# clock.net
KiCad netlist of a schematic drawn in EAGLE
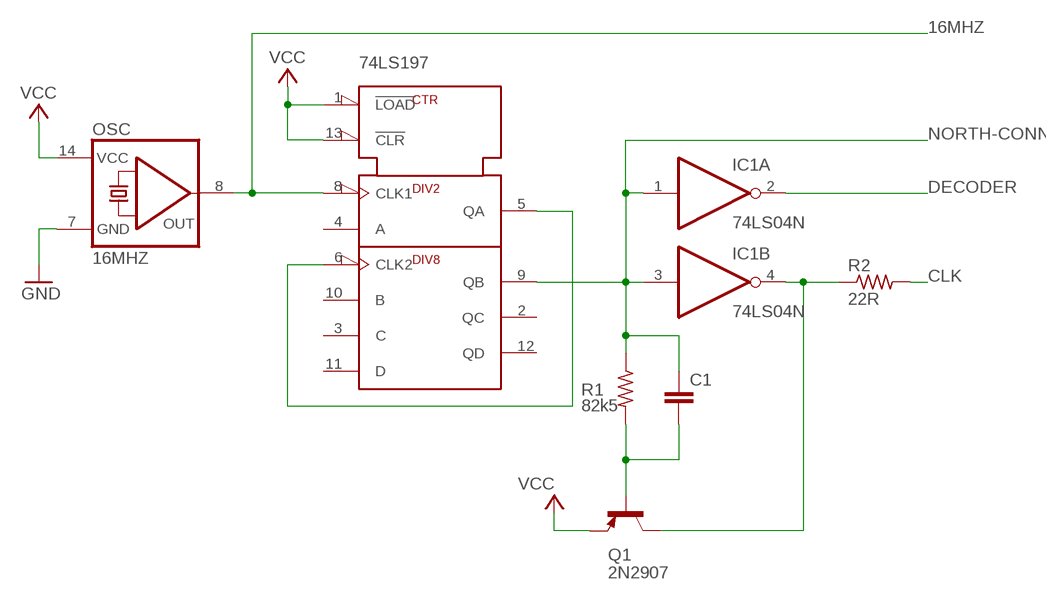
[diagram p0: schematic, sheet 1]

(export (version "E")
  (design (tool "Eeschema 10.0.6"))
  (components
    (comp (ref "C1")
      (value "C-EU025-024X044")
      (footprint "eagle-import:C025-024X044")
      (libsource (lib "eagle-import") (part "C-EU025-024X044"))
    )
    (comp (ref "IC1")
      (value "74LS04N")
      (footprint "eagle-import:DIL14")
      (libsource (lib "eagle-import") (part "7404NLS"))
    )
    (comp (ref "OSC")
      (value "16MHZ")
      (footprint "eagle-import:DIL14S")
      (libsource (lib "eagle-import") (part "QG5860"))
    )
    (comp (ref "Q1")
      (value "2N2907")
      (footprint "eagle-import:TO18")
      (libsource (lib "eagle-import") (part "2N2907"))
    )
    (comp (ref "R1")
      (value "82k5")
      (footprint "eagle-import:0207_10")
      (libsource (lib "eagle-import") (part "R-US_0207/10"))
    )
    (comp (ref "R2")
      (value "22R")
      (footprint "eagle-import:0207_10")
      (libsource (lib "eagle-import") (part "R-US_0207/10"))
    )
    (comp (ref "U$1")
      (value "74LS197")
      (footprint "eagle-import:DIL14")
      (libsource (lib "eagle-import") (part "74LS197"))
    )
  )
  (nets
    (net (code "1") (name "/16MHZ") (class "Default")
      (node (ref "OSC") (pin "8") (pinfunction "OUT_8") (pintype "output"))
      (node (ref "U$1") (pin "8") (pinfunction "CLK1_8") (pintype "input"))
    )
    (net (code "2") (name "/CLK") (class "Default")
      (node (ref "R2") (pin "2") (pinfunction "2_2") (pintype "passive"))
    )
    (net (code "3") (name "/DECODER") (class "Default")
      (node (ref "IC1") (pin "2") (pinfunction "O_2") (pintype "output"))
    )
    (net (code "4") (name "/NORTH-CONN") (class "Default")
      (node (ref "C1") (pin "1") (pinfunction "1_1") (pintype "passive"))
      (node (ref "IC1") (pin "1") (pinfunction "I_1") (pintype "input"))
      (node (ref "IC1") (pin "3") (pinfunction "I_3") (pintype "input"))
      (node (ref "R1") (pin "1") (pinfunction "1_1") (pintype "passive"))
      (node (ref "U$1") (pin "9") (pinfunction "QB_9") (pintype "output"))
    )
    (net (code "5") (name "GND") (class "Default")
      (node (ref "OSC") (pin "7") (pinfunction "GND_7") (pintype "power_in"))
    )
    (net (code "6") (name "Net-(IC1B-O)") (class "Default")
      (node (ref "IC1") (pin "4") (pinfunction "O_4") (pintype "output"))
      (node (ref "Q1") (pin "3") (pinfunction "C_3") (pintype "passive"))
      (node (ref "R2") (pin "1") (pinfunction "1_1") (pintype "passive"))
    )
    (net (code "7") (name "Net-(Q1-B)") (class "Default")
      (node (ref "C1") (pin "2") (pinfunction "2_2") (pintype "passive"))
      (node (ref "Q1") (pin "2") (pinfunction "B_2") (pintype "passive"))
      (node (ref "R1") (pin "2") (pinfunction "2_2") (pintype "passive"))
    )
    (net (code "8") (name "Net-(U$1A-CLK2)") (class "Default")
      (node (ref "U$1") (pin "5") (pinfunction "QA_5") (pintype "output"))
      (node (ref "U$1") (pin "6") (pinfunction "CLK2_6") (pintype "input"))
    )
    (net (code "9") (name "VCC") (class "Default")
      (node (ref "OSC") (pin "14") (pinfunction "VCC_14") (pintype "power_in"))
      (node (ref "Q1") (pin "1") (pinfunction "E_1") (pintype "passive"))
      (node (ref "U$1") (pin "1") (pinfunction "~{LOAD}_1") (pintype "input"))
      (node (ref "U$1") (pin "13") (pinfunction "~{CLR}_13") (pintype "input"))
    )
    (net (code "10") (name "unconnected-(U$1A-A-Pad4)") (class "Default")
      (node (ref "U$1") (pin "4") (pinfunction "A_4") (pintype "input"))
    )
    (net (code "11") (name "unconnected-(U$1A-B-Pad10)") (class "Default")
      (node (ref "U$1") (pin "10") (pinfunction "B_10") (pintype "input"))
    )
    (net (code "12") (name "unconnected-(U$1A-C-Pad3)") (class "Default")
      (node (ref "U$1") (pin "3") (pinfunction "C_3") (pintype "input"))
    )
    (net (code "13") (name "unconnected-(U$1A-D-Pad11)") (class "Default")
      (node (ref "U$1") (pin "11") (pinfunction "D_11") (pintype "input"))
    )
    (net (code "14") (name "unconnected-(U$1A-QC-Pad2)") (class "Default")
      (node (ref "U$1") (pin "2") (pinfunction "QC_2") (pintype "output"))
    )
    (net (code "15") (name "unconnected-(U$1A-QD-Pad12)") (class "Default")
      (node (ref "U$1") (pin "12") (pinfunction "QD_12") (pintype "output"))
    )
  )
)
